# pixpi.net
KiCad netlist of a schematic drawn in EAGLE
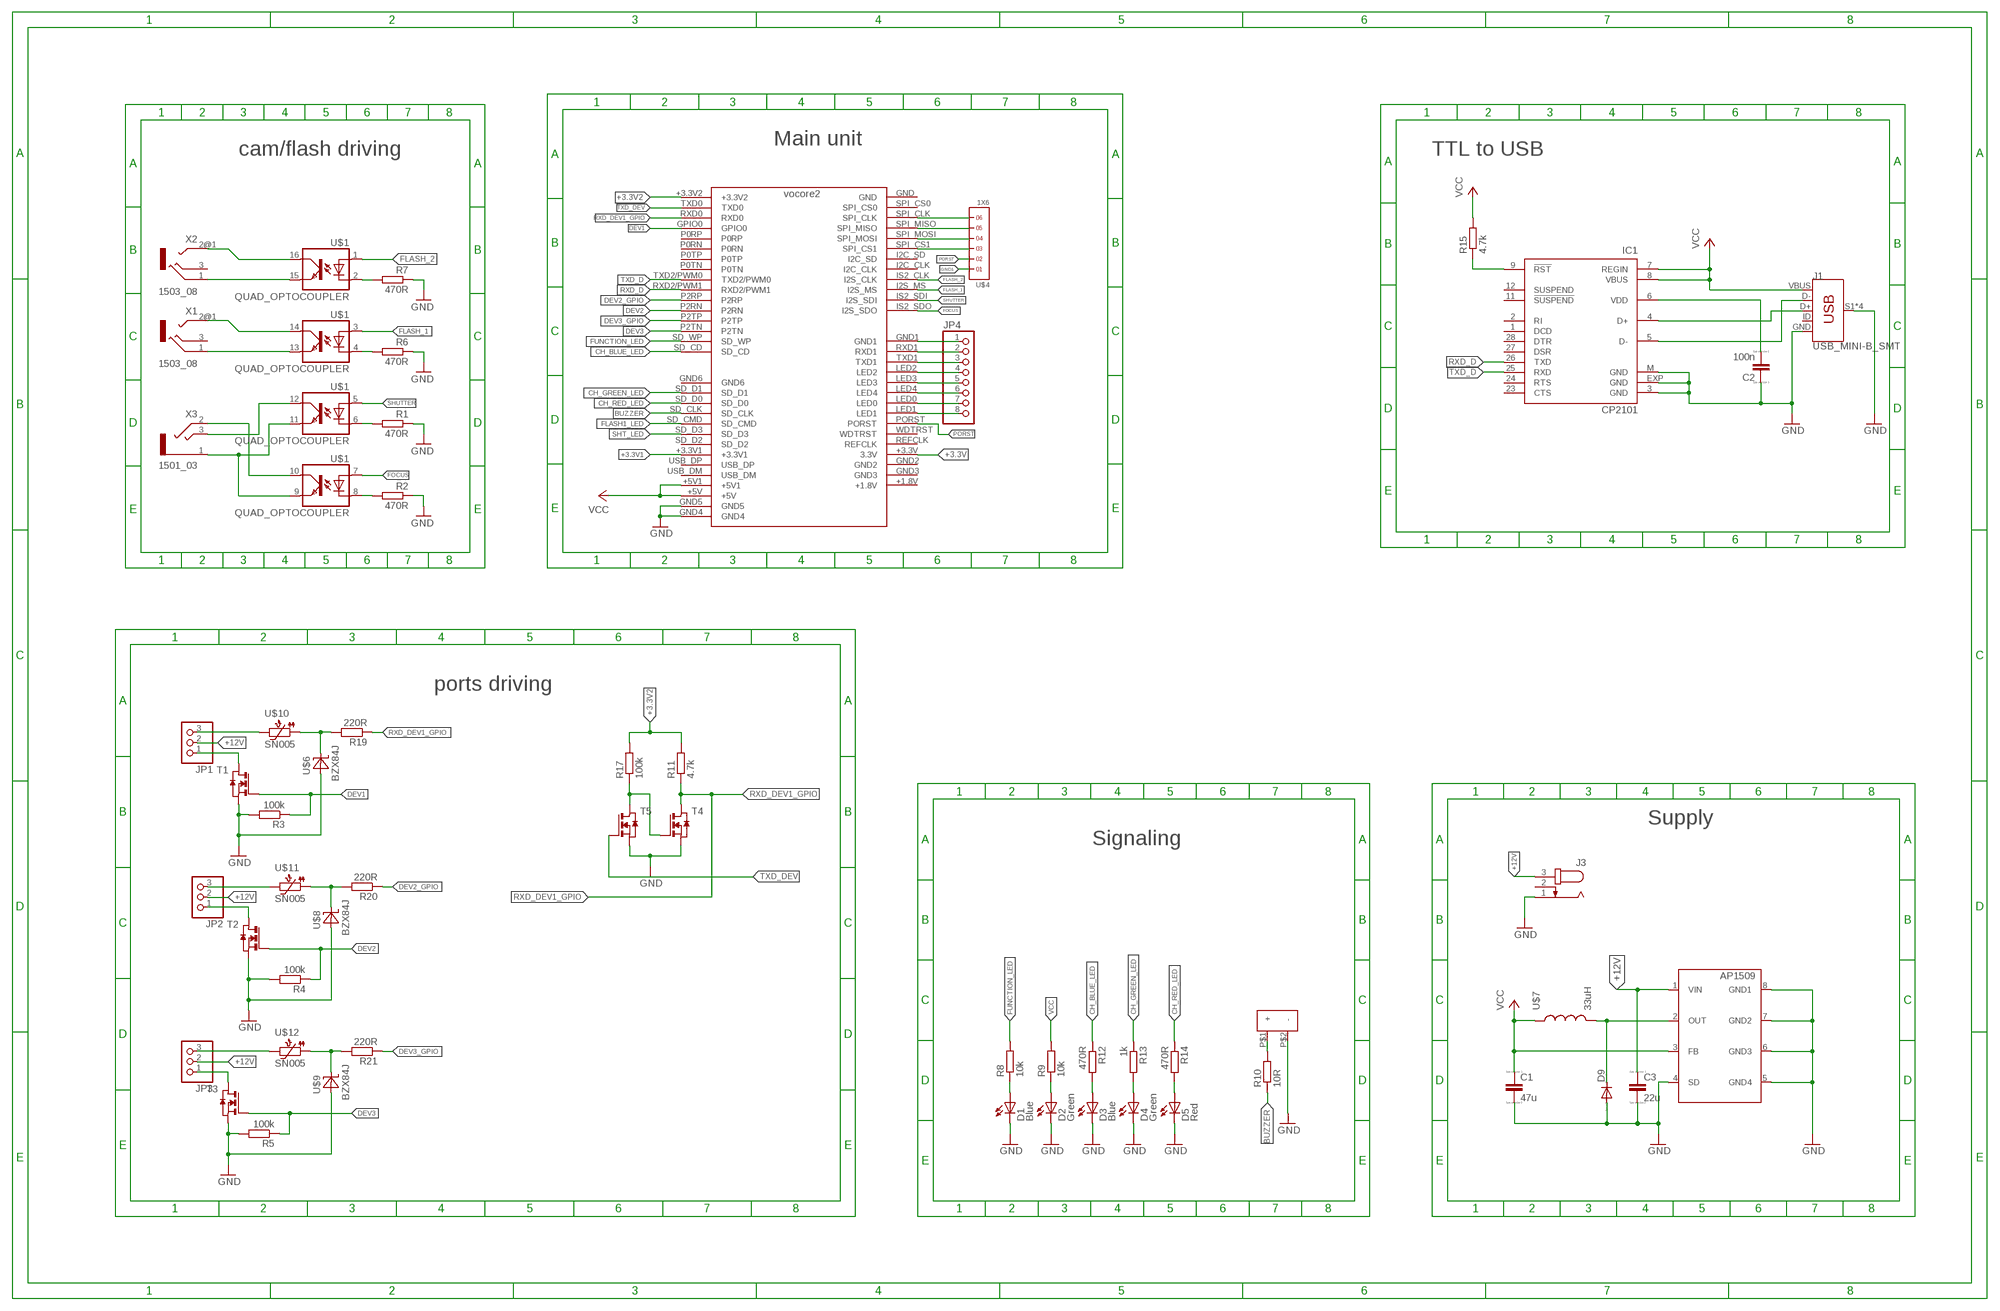
[diagram p0: schematic, sheet 1]

(export (version "E")
  (design (tool "Eeschema 10.0.6"))
  (components
    (comp (ref "C1")
      (value "47u")
      (footprint "eagle-import:C1210")
      (libsource (lib "eagle-import") (part "CC1210"))
    )
    (comp (ref "C2")
      (value "100n")
      (footprint "eagle-import:C0805")
      (libsource (lib "eagle-import") (part "C"))
    )
    (comp (ref "C3")
      (value "22u")
      (footprint "eagle-import:C1210")
      (libsource (lib "eagle-import") (part "CC1210"))
    )
    (comp (ref "D1")
      (value "Blue")
      (footprint "eagle-import:CHIPLED_0603")
      (fields (field (name "SPICEPREFIX") "D"))
      (libsource (lib "eagle-import") (part "LEDCHIPLED_0603"))
    )
    (comp (ref "D2")
      (value "Green")
      (footprint "eagle-import:CHIPLED_0603")
      (libsource (lib "eagle-import") (part "LEDCHIPLED_0603"))
    )
    (comp (ref "D3")
      (value "Blue")
      (footprint "eagle-import:CHIPLED_1206")
      (libsource (lib "eagle-import") (part "LEDCHIPLED_1206"))
    )
    (comp (ref "D4")
      (value "Green")
      (footprint "eagle-import:CHIPLED_1206")
      (libsource (lib "eagle-import") (part "LEDCHIPLED_1206"))
    )
    (comp (ref "D5")
      (value "Red")
      (footprint "eagle-import:CHIPLED_1206")
      (libsource (lib "eagle-import") (part "LEDCHIPLED_1206"))
    )
    (comp (ref "D9")
      (value "DIODE-SOD323-W")
      (footprint "eagle-import:SOD323-W")
      (libsource (lib "eagle-import") (part "DIODE-SOD323-W"))
    )
    (comp (ref "IC1")
      (value "CP2101")
      (footprint "eagle-import:MLP28")
      (fields (field (name "MF") "FARNELL") (field (name "MPN") "CP2102-GM"))
      (libsource (lib "eagle-import") (part "CP2101"))
    )
    (comp (ref "J1")
      (value "USB_MINI-B_SMT")
      (footprint "eagle-import:USB-MINIB")
      (libsource (lib "eagle-import") (part "USB_MINI-B_SMT"))
    )
    (comp (ref "J3")
      (value "JACK-PLUG0")
      (footprint "eagle-import:SPC4077")
      (libsource (lib "eagle-import") (part "JACK-PLUG0"))
    )
    (comp (ref "JP1")
      (value "PINHD-1X3/90")
      (footprint "eagle-import:1X03_90")
      (libsource (lib "eagle-import") (part "PINHD-1X3/90"))
    )
    (comp (ref "JP2")
      (value "PINHD-1X3/90")
      (footprint "eagle-import:1X03_90")
      (libsource (lib "eagle-import") (part "PINHD-1X3/90"))
    )
    (comp (ref "JP3")
      (value "PINHD-1X3/90")
      (footprint "eagle-import:1X03_90")
      (libsource (lib "eagle-import") (part "PINHD-1X3/90"))
    )
    (comp (ref "JP4")
      (value "PINHD-1X8")
      (footprint "eagle-import:1X08")
      (libsource (lib "eagle-import") (part "PINHD-1X8"))
    )
    (comp (ref "R1")
      (value "470R")
      (footprint "eagle-import:R0805")
      (libsource (lib "eagle-import") (part "R-EU_R0805"))
    )
    (comp (ref "R2")
      (value "470R")
      (footprint "eagle-import:R0805")
      (libsource (lib "eagle-import") (part "R-EU_R0805"))
    )
    (comp (ref "R3")
      (value "100k")
      (footprint "eagle-import:R0805")
      (libsource (lib "eagle-import") (part "R-EU_R0805"))
    )
    (comp (ref "R4")
      (value "100k")
      (footprint "eagle-import:R0805")
      (libsource (lib "eagle-import") (part "R-EU_R0805"))
    )
    (comp (ref "R5")
      (value "100k")
      (footprint "eagle-import:R0805")
      (libsource (lib "eagle-import") (part "R-EU_R0805"))
    )
    (comp (ref "R6")
      (value "470R")
      (footprint "eagle-import:R0805")
      (libsource (lib "eagle-import") (part "R-EU_R0805"))
    )
    (comp (ref "R7")
      (value "470R")
      (footprint "eagle-import:R0805")
      (libsource (lib "eagle-import") (part "R-EU_R0805"))
    )
    (comp (ref "R8")
      (value "10k")
      (footprint "eagle-import:R0805")
      (libsource (lib "eagle-import") (part "R-EU_R0805"))
    )
    (comp (ref "R9")
      (value "10k")
      (footprint "eagle-import:R0805")
      (libsource (lib "eagle-import") (part "R-EU_R0805"))
    )
    (comp (ref "R10")
      (value "10R")
      (footprint "eagle-import:R0805")
      (libsource (lib "eagle-import") (part "R-EU_R0805"))
    )
    (comp (ref "R11")
      (value "4.7k")
      (footprint "eagle-import:R0805")
      (libsource (lib "eagle-import") (part "R-EU_R0805"))
    )
    (comp (ref "R12")
      (value "470R")
      (footprint "eagle-import:R0805")
      (libsource (lib "eagle-import") (part "R-EU_R0805"))
    )
    (comp (ref "R13")
      (value "1k")
      (footprint "eagle-import:R0805")
      (libsource (lib "eagle-import") (part "R-EU_R0805"))
    )
    (comp (ref "R14")
      (value "470R")
      (footprint "eagle-import:R0805")
      (libsource (lib "eagle-import") (part "R-EU_R0805"))
    )
    (comp (ref "R15")
      (value "4.7k")
      (footprint "eagle-import:R0805")
      (libsource (lib "eagle-import") (part "R-EU_R0805"))
    )
    (comp (ref "R17")
      (value "100k")
      (footprint "eagle-import:R0805")
      (libsource (lib "eagle-import") (part "R-EU_R0805"))
    )
    (comp (ref "R19")
      (value "220R")
      (footprint "eagle-import:R0805")
      (libsource (lib "eagle-import") (part "R-EU_R0805"))
    )
    (comp (ref "R20")
      (value "220R")
      (footprint "eagle-import:R0805")
      (libsource (lib "eagle-import") (part "R-EU_R0805"))
    )
    (comp (ref "R21")
      (value "220R")
      (footprint "eagle-import:R0805")
      (libsource (lib "eagle-import") (part "R-EU_R0805"))
    )
    (comp (ref "T1")
      (value "NMOSSOT23")
      (footprint "eagle-import:SOT-23")
      (libsource (lib "eagle-import") (part "NMOSSOT23"))
    )
    (comp (ref "T2")
      (value "NMOSSOT23")
      (footprint "eagle-import:SOT-23")
      (libsource (lib "eagle-import") (part "NMOSSOT23"))
    )
    (comp (ref "T3")
      (value "NMOSSOT23")
      (footprint "eagle-import:SOT-23")
      (libsource (lib "eagle-import") (part "NMOSSOT23"))
    )
    (comp (ref "T4")
      (value "NMOSSOT23")
      (footprint "eagle-import:SOT-23")
      (libsource (lib "eagle-import") (part "NMOSSOT23"))
    )
    (comp (ref "T5")
      (value "NMOSSOT23")
      (footprint "eagle-import:SOT-23")
      (libsource (lib "eagle-import") (part "NMOSSOT23"))
    )
    (comp (ref "U$1")
      (value "QUAD_OPTOCOUPLER")
      (footprint "eagle-import:SO16")
      (libsource (lib "eagle-import") (part "QUAD_OPTOCOUPLER"))
    )
    (comp (ref "U$2")
      (value "VOCORE2")
      (footprint "eagle-import:VOCORE2")
      (libsource (lib "eagle-import") (part "VOCORE2"))
    )
    (comp (ref "U$3")
      (value "LD-BZEG-0905")
      (footprint "eagle-import:LD-BZEG-0905")
      (libsource (lib "eagle-import") (part "LD-BZEG-0905"))
    )
    (comp (ref "U$4")
      (value "1X6")
      (footprint "eagle-import:1X6")
      (libsource (lib "eagle-import") (part "1X6"))
    )
    (comp (ref "U$5")
      (value "AP1509")
      (footprint "eagle-import:SOP08")
      (libsource (lib "eagle-import") (part "AP1509"))
    )
    (comp (ref "U$6")
      (value "BZX84J")
      (footprint "eagle-import:SOD323_ST")
      (libsource (lib "eagle-import") (part "BZX84J"))
    )
    (comp (ref "U$7")
      (value "33uH")
      (footprint "eagle-import:DJNR6028")
      (libsource (lib "eagle-import") (part "DJNR6028"))
    )
    (comp (ref "U$8")
      (value "BZX84J")
      (footprint "eagle-import:SOD323_ST")
      (libsource (lib "eagle-import") (part "BZX84J"))
    )
    (comp (ref "U$9")
      (value "BZX84J")
      (footprint "eagle-import:SOD323_ST")
      (libsource (lib "eagle-import") (part "BZX84J"))
    )
    (comp (ref "U$10")
      (value "SN005")
      (footprint "eagle-import:R1206")
      (libsource (lib "eagle-import") (part "SN005"))
    )
    (comp (ref "U$11")
      (value "SN005")
      (footprint "eagle-import:R1206")
      (libsource (lib "eagle-import") (part "SN005"))
    )
    (comp (ref "U$12")
      (value "SN005")
      (footprint "eagle-import:R1206")
      (libsource (lib "eagle-import") (part "SN005"))
    )
    (comp (ref "X1")
      (value "1503_08")
      (footprint "eagle-import:1503_08")
      (libsource (lib "eagle-import") (part "1503_?08"))
    )
    (comp (ref "X2")
      (value "1503_08")
      (footprint "eagle-import:1503_08")
      (libsource (lib "eagle-import") (part "1503_?08"))
    )
    (comp (ref "X3")
      (value "1501_03")
      (footprint "eagle-import:1501_03")
      (libsource (lib "eagle-import") (part "1501_03"))
    )
  )
  (nets
    (net (code "1") (name "+3.3V") (class "Default")
      (node (ref "U$2") (pin "+3.3V") (pinfunction "3.3V_+3.3V") (pintype "bidirectional"))
    )
    (net (code "2") (name "+3.3V1") (class "Default")
      (node (ref "U$2") (pin "+3.3V1") (pinfunction "+3.3V1_+3.3V1") (pintype "bidirectional"))
    )
    (net (code "3") (name "+3.3V2") (class "Default")
      (node (ref "R11") (pin "2") (pinfunction "2_2") (pintype "passive"))
      (node (ref "R17") (pin "2") (pinfunction "2_2") (pintype "passive"))
      (node (ref "U$2") (pin "+3.3V2") (pinfunction "+3.3V2_+3.3V2") (pintype "bidirectional"))
    )
    (net (code "4") (name "+12V") (class "Default")
      (node (ref "C3") (pin "1") (pinfunction "1_1") (pintype "passive"))
      (node (ref "J3") (pin "3") (pinfunction "3_3") (pintype "passive"))
      (node (ref "JP1") (pin "2") (pinfunction "2_2") (pintype "passive"))
      (node (ref "JP2") (pin "2") (pinfunction "2_2") (pintype "passive"))
      (node (ref "JP3") (pin "2") (pinfunction "2_2") (pintype "passive"))
      (node (ref "U$5") (pin "1") (pinfunction "VIN_1") (pintype "bidirectional"))
    )
    (net (code "5") (name "BUZZER") (class "Default")
      (node (ref "R10") (pin "1") (pinfunction "1_1") (pintype "passive"))
      (node (ref "U$2") (pin "SD_CLK") (pinfunction "SD_CLK_SD_CLK") (pintype "bidirectional"))
    )
    (net (code "6") (name "CH_BLUE_LED") (class "Default")
      (node (ref "R12") (pin "1") (pinfunction "1_1") (pintype "passive"))
      (node (ref "U$2") (pin "SD_CD") (pinfunction "SD_CD_SD_CD") (pintype "bidirectional"))
    )
    (net (code "7") (name "CH_GREEN_LED") (class "Default")
      (node (ref "R13") (pin "1") (pinfunction "1_1") (pintype "passive"))
      (node (ref "U$2") (pin "SD_D1") (pinfunction "SD_D1_SD_D1") (pintype "bidirectional"))
    )
    (net (code "8") (name "CH_RED_LED") (class "Default")
      (node (ref "R14") (pin "1") (pinfunction "1_1") (pintype "passive"))
      (node (ref "U$2") (pin "SD_D0") (pinfunction "SD_D0_SD_D0") (pintype "bidirectional"))
    )
    (net (code "9") (name "DEV1") (class "Default")
      (node (ref "R3") (pin "1") (pinfunction "1_1") (pintype "passive"))
      (node (ref "T1") (pin "3") (pinfunction "G_3") (pintype "passive"))
      (node (ref "U$2") (pin "GPIO0") (pinfunction "GPIO0_GPIO0") (pintype "bidirectional"))
    )
    (net (code "10") (name "DEV2") (class "Default")
      (node (ref "R4") (pin "1") (pinfunction "1_1") (pintype "passive"))
      (node (ref "T2") (pin "3") (pinfunction "G_3") (pintype "passive"))
      (node (ref "U$2") (pin "P2RN") (pinfunction "P2RN_P2RN") (pintype "bidirectional"))
    )
    (net (code "11") (name "DEV2_GPIO") (class "Default")
      (node (ref "R20") (pin "1") (pinfunction "1_1") (pintype "passive"))
      (node (ref "U$2") (pin "P2RP") (pinfunction "P2RP_P2RP") (pintype "bidirectional"))
    )
    (net (code "12") (name "DEV3") (class "Default")
      (node (ref "R5") (pin "1") (pinfunction "1_1") (pintype "passive"))
      (node (ref "T3") (pin "3") (pinfunction "G_3") (pintype "passive"))
      (node (ref "U$2") (pin "P2TN") (pinfunction "P2TN_P2TN") (pintype "bidirectional"))
    )
    (net (code "13") (name "DEV3_GPIO") (class "Default")
      (node (ref "R21") (pin "1") (pinfunction "1_1") (pintype "passive"))
      (node (ref "U$2") (pin "P2TP") (pinfunction "P2TP_P2TP") (pintype "bidirectional"))
    )
    (net (code "14") (name "FLASH1_LED") (class "Default")
      (node (ref "U$2") (pin "SD_CMD") (pinfunction "SD_CMD_SD_CMD") (pintype "bidirectional"))
    )
    (net (code "15") (name "FLASH_1") (class "Default")
      (node (ref "U$1") (pin "3") (pinfunction "A1_3") (pintype "passive"))
      (node (ref "U$2") (pin "I2S_MS") (pinfunction "I2S_MS_I2S_MS") (pintype "bidirectional"))
    )
    (net (code "16") (name "FLASH_2") (class "Default")
      (node (ref "U$1") (pin "1") (pinfunction "A_1") (pintype "passive"))
      (node (ref "U$2") (pin "IS2_CLK") (pinfunction "I2S_CLK_IS2_CLK") (pintype "bidirectional"))
    )
    (net (code "17") (name "FOCUS") (class "Default")
      (node (ref "U$1") (pin "7") (pinfunction "A3_7") (pintype "passive"))
      (node (ref "U$2") (pin "IS2_SDO") (pinfunction "I2S_SDO_IS2_SDO") (pintype "bidirectional"))
    )
    (net (code "18") (name "FUNCTION_LED") (class "Default")
      (node (ref "R8") (pin "2") (pinfunction "2_2") (pintype "passive"))
      (node (ref "U$2") (pin "SD_WP") (pinfunction "SD_WP_SD_WP") (pintype "bidirectional"))
    )
    (net (code "19") (name "GND") (class "Default")
      (node (ref "C1") (pin "2") (pinfunction "2_2") (pintype "passive"))
      (node (ref "C2") (pin "1") (pinfunction "1_1") (pintype "passive"))
      (node (ref "C3") (pin "2") (pinfunction "2_2") (pintype "passive"))
      (node (ref "D1") (pin "C") (pinfunction "C_C") (pintype "passive"))
      (node (ref "D2") (pin "C") (pinfunction "C_C") (pintype "passive"))
      (node (ref "D3") (pin "C") (pinfunction "C_C") (pintype "passive"))
      (node (ref "D4") (pin "C") (pinfunction "C_C") (pintype "passive"))
      (node (ref "D5") (pin "C") (pinfunction "C_C") (pintype "passive"))
      (node (ref "D9") (pin "A") (pinfunction "A_A") (pintype "passive"))
      (node (ref "IC1") (pin "3") (pinfunction "GND_3") (pintype "power_in"))
      (node (ref "IC1") (pin "EXP") (pinfunction "GND_EXP") (pintype "power_in"))
      (node (ref "IC1") (pin "M") (pinfunction "GND_M") (pintype "power_in"))
      (node (ref "J1") (pin "GND") (pinfunction "GND_GND") (pintype "power_in"))
      (node (ref "J1") (pin "S1") (pinfunction "SHIELD_S1") (pintype "bidirectional"))
      (node (ref "J1") (pin "S2") (pinfunction "SHIELD_S2") (pintype "bidirectional"))
      (node (ref "J1") (pin "S3") (pinfunction "SHIELD_S3") (pintype "bidirectional"))
      (node (ref "J1") (pin "S4") (pinfunction "SHIELD_S4") (pintype "bidirectional"))
      (node (ref "J3") (pin "1") (pinfunction "1_1") (pintype "passive"))
      (node (ref "R1") (pin "1") (pinfunction "1_1") (pintype "passive"))
      (node (ref "R2") (pin "1") (pinfunction "1_1") (pintype "passive"))
      (node (ref "R3") (pin "2") (pinfunction "2_2") (pintype "passive"))
      (node (ref "R4") (pin "2") (pinfunction "2_2") (pintype "passive"))
      (node (ref "R5") (pin "2") (pinfunction "2_2") (pintype "passive"))
      (node (ref "R6") (pin "1") (pinfunction "1_1") (pintype "passive"))
      (node (ref "R7") (pin "1") (pinfunction "1_1") (pintype "passive"))
      (node (ref "T1") (pin "2") (pinfunction "S_2") (pintype "passive"))
      (node (ref "T2") (pin "2") (pinfunction "S_2") (pintype "passive"))
      (node (ref "T3") (pin "2") (pinfunction "S_2") (pintype "passive"))
      (node (ref "T4") (pin "2") (pinfunction "S_2") (pintype "passive"))
      (node (ref "T5") (pin "2") (pinfunction "S_2") (pintype "passive"))
      (node (ref "U$2") (pin "GND4") (pinfunction "GND4_GND4") (pintype "bidirectional"))
      (node (ref "U$2") (pin "GND5") (pinfunction "GND5_GND5") (pintype "bidirectional"))
      (node (ref "U$3") (pin "P$2") (pinfunction "-_P$2") (pintype "bidirectional"))
      (node (ref "U$5") (pin "4") (pinfunction "SD_4") (pintype "bidirectional"))
      (node (ref "U$5") (pin "5") (pinfunction "GND4_5") (pintype "bidirectional"))
      (node (ref "U$5") (pin "6") (pinfunction "GND3_6") (pintype "bidirectional"))
      (node (ref "U$5") (pin "7") (pinfunction "GND2_7") (pintype "bidirectional"))
      (node (ref "U$5") (pin "8") (pinfunction "GND1_8") (pintype "bidirectional"))
      (node (ref "U$6") (pin "A") (pinfunction "A_A") (pintype "passive"))
      (node (ref "U$8") (pin "A") (pinfunction "A_A") (pintype "passive"))
      (node (ref "U$9") (pin "A") (pinfunction "A_A") (pintype "passive"))
    )
    (net (code "20") (name "GND1") (class "Default")
      (node (ref "JP4") (pin "1") (pinfunction "1_1") (pintype "passive"))
      (node (ref "U$2") (pin "GND1") (pinfunction "GND1_GND1") (pintype "bidirectional"))
      (node (ref "U$4") (pin "1") (pinfunction "1_1") (pintype "bidirectional"))
    )
    (net (code "21") (name "Net-(D1-PadA)") (class "Default")
      (node (ref "D1") (pin "A") (pinfunction "A_A") (pintype "passive"))
      (node (ref "R8") (pin "1") (pinfunction "1_1") (pintype "passive"))
    )
    (net (code "22") (name "Net-(D2-PadA)") (class "Default")
      (node (ref "D2") (pin "A") (pinfunction "A_A") (pintype "passive"))
      (node (ref "R9") (pin "1") (pinfunction "1_1") (pintype "passive"))
    )
    (net (code "23") (name "Net-(D3-PadA)") (class "Default")
      (node (ref "D3") (pin "A") (pinfunction "A_A") (pintype "passive"))
      (node (ref "R12") (pin "2") (pinfunction "2_2") (pintype "passive"))
    )
    (net (code "24") (name "Net-(D4-PadA)") (class "Default")
      (node (ref "D4") (pin "A") (pinfunction "A_A") (pintype "passive"))
      (node (ref "R13") (pin "2") (pinfunction "2_2") (pintype "passive"))
    )
    (net (code "25") (name "Net-(D5-PadA)") (class "Default")
      (node (ref "D5") (pin "A") (pinfunction "A_A") (pintype "passive"))
      (node (ref "R14") (pin "2") (pinfunction "2_2") (pintype "passive"))
    )
    (net (code "26") (name "Net-(IC1-D+)") (class "Default")
      (node (ref "IC1") (pin "4") (pinfunction "D+_4") (pintype "bidirectional"))
      (node (ref "J1") (pin "D+") (pinfunction "D+_D+") (pintype "bidirectional"))
    )
    (net (code "27") (name "Net-(IC1-D-)") (class "Default")
      (node (ref "IC1") (pin "5") (pinfunction "D-_5") (pintype "bidirectional"))
      (node (ref "J1") (pin "D-") (pinfunction "D-_D-") (pintype "bidirectional"))
    )
    (net (code "28") (name "Net-(IC1-VDD)") (class "Default")
      (node (ref "C2") (pin "2") (pinfunction "2_2") (pintype "passive"))
      (node (ref "IC1") (pin "6") (pinfunction "VDD_6") (pintype "power_in"))
    )
    (net (code "29") (name "Net-(IC1-~{RST})") (class "Default")
      (node (ref "IC1") (pin "9") (pinfunction "~{RST}_9") (pintype "bidirectional"))
      (node (ref "R15") (pin "1") (pinfunction "1_1") (pintype "passive"))
    )
    (net (code "30") (name "Net-(JP1-Pad3)") (class "Default")
      (node (ref "JP1") (pin "3") (pinfunction "3_3") (pintype "passive"))
      (node (ref "U$10") (pin "2") (pinfunction "2_2") (pintype "passive"))
    )
    (net (code "31") (name "Net-(JP2-Pad3)") (class "Default")
      (node (ref "JP2") (pin "3") (pinfunction "3_3") (pintype "passive"))
      (node (ref "U$11") (pin "2") (pinfunction "2_2") (pintype "passive"))
    )
    (net (code "32") (name "Net-(JP3-Pad3)") (class "Default")
      (node (ref "JP3") (pin "3") (pinfunction "3_3") (pintype "passive"))
      (node (ref "U$12") (pin "2") (pinfunction "2_2") (pintype "passive"))
    )
    (net (code "33") (name "Net-(JP4-Pad2)") (class "Default")
      (node (ref "JP4") (pin "2") (pinfunction "2_2") (pintype "passive"))
      (node (ref "U$2") (pin "RXD1") (pinfunction "RXD1_RXD1") (pintype "bidirectional"))
    )
    (net (code "34") (name "Net-(JP4-Pad3)") (class "Default")
      (node (ref "JP4") (pin "3") (pinfunction "3_3") (pintype "passive"))
      (node (ref "U$2") (pin "TXD1") (pinfunction "TXD1_TXD1") (pintype "bidirectional"))
    )
    (net (code "35") (name "Net-(JP4-Pad4)") (class "Default")
      (node (ref "JP4") (pin "4") (pinfunction "4_4") (pintype "passive"))
      (node (ref "U$2") (pin "LED2") (pinfunction "LED2_LED2") (pintype "bidirectional"))
    )
    (net (code "36") (name "Net-(JP4-Pad5)") (class "Default")
      (node (ref "JP4") (pin "5") (pinfunction "5_5") (pintype "passive"))
      (node (ref "U$2") (pin "LED3") (pinfunction "LED3_LED3") (pintype "bidirectional"))
    )
    (net (code "37") (name "Net-(JP4-Pad6)") (class "Default")
      (node (ref "JP4") (pin "6") (pinfunction "6_6") (pintype "passive"))
      (node (ref "U$2") (pin "LED4") (pinfunction "LED4_LED4") (pintype "bidirectional"))
    )
    (net (code "38") (name "Net-(JP4-Pad7)") (class "Default")
      (node (ref "JP4") (pin "7") (pinfunction "7_7") (pintype "passive"))
      (node (ref "U$2") (pin "LED0") (pinfunction "LED0_LED0") (pintype "bidirectional"))
    )
    (net (code "39") (name "Net-(JP4-Pad8)") (class "Default")
      (node (ref "JP4") (pin "8") (pinfunction "8_8") (pintype "passive"))
      (node (ref "U$2") (pin "LED1") (pinfunction "LED1_LED1") (pintype "bidirectional"))
    )
    (net (code "40") (name "Net-(R19-Pad2)") (class "Default")
      (node (ref "R19") (pin "2") (pinfunction "2_2") (pintype "passive"))
      (node (ref "U$10") (pin "1") (pinfunction "1_1") (pintype "passive"))
      (node (ref "U$6") (pin "C") (pinfunction "C_C") (pintype "passive"))
    )
    (net (code "41") (name "Net-(R20-Pad2)") (class "Default")
      (node (ref "R20") (pin "2") (pinfunction "2_2") (pintype "passive"))
      (node (ref "U$11") (pin "1") (pinfunction "1_1") (pintype "passive"))
      (node (ref "U$8") (pin "C") (pinfunction "C_C") (pintype "passive"))
    )
    (net (code "42") (name "Net-(R21-Pad2)") (class "Default")
      (node (ref "R21") (pin "2") (pinfunction "2_2") (pintype "passive"))
      (node (ref "U$12") (pin "1") (pinfunction "1_1") (pintype "passive"))
      (node (ref "U$9") (pin "C") (pinfunction "C_C") (pintype "passive"))
    )
    (net (code "43") (name "Net-(T1-D)") (class "Default")
      (node (ref "JP1") (pin "1") (pinfunction "1_1") (pintype "passive"))
      (node (ref "T1") (pin "1") (pinfunction "D_1") (pintype "passive"))
    )
    (net (code "44") (name "Net-(T2-D)") (class "Default")
      (node (ref "JP2") (pin "1") (pinfunction "1_1") (pintype "passive"))
      (node (ref "T2") (pin "1") (pinfunction "D_1") (pintype "passive"))
    )
    (net (code "45") (name "Net-(T3-D)") (class "Default")
      (node (ref "JP3") (pin "1") (pinfunction "1_1") (pintype "passive"))
      (node (ref "T3") (pin "1") (pinfunction "D_1") (pintype "passive"))
    )
    (net (code "46") (name "Net-(T4-G)") (class "Default")
      (node (ref "R17") (pin "1") (pinfunction "1_1") (pintype "passive"))
      (node (ref "T4") (pin "3") (pinfunction "G_3") (pintype "passive"))
      (node (ref "T5") (pin "1") (pinfunction "D_1") (pintype "passive"))
    )
    (net (code "47") (name "Net-(U$1-C)") (class "Default")
      (node (ref "R7") (pin "2") (pinfunction "2_2") (pintype "passive"))
      (node (ref "U$1") (pin "2") (pinfunction "C_2") (pintype "passive"))
    )
    (net (code "48") (name "Net-(U$1-C1)") (class "Default")
      (node (ref "R6") (pin "2") (pinfunction "2_2") (pintype "passive"))
      (node (ref "U$1") (pin "4") (pinfunction "C1_4") (pintype "passive"))
    )
    (net (code "49") (name "Net-(U$1-C2)") (class "Default")
      (node (ref "R1") (pin "2") (pinfunction "2_2") (pintype "passive"))
      (node (ref "U$1") (pin "6") (pinfunction "C2_6") (pintype "passive"))
    )
    (net (code "50") (name "Net-(U$1-C3)") (class "Default")
      (node (ref "R2") (pin "2") (pinfunction "2_2") (pintype "passive"))
      (node (ref "U$1") (pin "8") (pinfunction "C3_8") (pintype "passive"))
    )
    (net (code "51") (name "Net-(U$1-COL)") (class "Default")
      (node (ref "U$1") (pin "16") (pinfunction "COL_16") (pintype "passive"))
      (node (ref "X2") (pin "2@1") (pinfunction "2_2@1") (pintype "passive"))
    )
    (net (code "52") (name "Net-(U$1-COL1)") (class "Default")
      (node (ref "U$1") (pin "14") (pinfunction "COL1_14") (pintype "passive"))
      (node (ref "X1") (pin "2@1") (pinfunction "2_2@1") (pintype "passive"))
    )
    (net (code "53") (name "Net-(U$1-COL2)") (class "Default")
      (node (ref "U$1") (pin "12") (pinfunction "COL2_12") (pintype "passive"))
      (node (ref "X3") (pin "3") (pinfunction "3_3") (pintype "passive"))
    )
    (net (code "54") (name "Net-(U$1-COL3)") (class "Default")
      (node (ref "U$1") (pin "10") (pinfunction "COL3_10") (pintype "passive"))
      (node (ref "X3") (pin "2") (pinfunction "2_2") (pintype "passive"))
    )
    (net (code "55") (name "Net-(U$1-EMIT)") (class "Default")
      (node (ref "U$1") (pin "15") (pinfunction "EMIT_15") (pintype "passive"))
      (node (ref "X2") (pin "1") (pinfunction "1_1") (pintype "passive"))
    )
    (net (code "56") (name "Net-(U$1-EMIT1)") (class "Default")
      (node (ref "U$1") (pin "13") (pinfunction "EMIT1_13") (pintype "passive"))
      (node (ref "X1") (pin "1") (pinfunction "1_1") (pintype "passive"))
    )
    (net (code "57") (name "Net-(U$1-EMIT2)") (class "Default")
      (node (ref "U$1") (pin "11") (pinfunction "EMIT2_11") (pintype "passive"))
      (node (ref "U$1") (pin "9") (pinfunction "EMIT3_9") (pintype "passive"))
      (node (ref "X3") (pin "1") (pinfunction "1_1") (pintype "passive"))
    )
    (net (code "58") (name "Net-(U$2-PadSPI_CLK)") (class "Default")
      (node (ref "U$2") (pin "SPI_CLK") (pinfunction "SPI_CLK_SPI_CLK") (pintype "bidirectional"))
      (node (ref "U$4") (pin "6") (pinfunction "6_6") (pintype "bidirectional"))
    )
    (net (code "59") (name "Net-(U$2-PadSPI_CS1)") (class "Default")
      (node (ref "U$2") (pin "SPI_CS1") (pinfunction "SPI_CS1_SPI_CS1") (pintype "bidirectional"))
      (node (ref "U$4") (pin "3") (pinfunction "3_3") (pintype "bidirectional"))
    )
    (net (code "60") (name "Net-(U$2-PadSPI_MISO)") (class "Default")
      (node (ref "U$2") (pin "SPI_MISO") (pinfunction "SPI_MISO_SPI_MISO") (pintype "bidirectional"))
      (node (ref "U$4") (pin "5") (pinfunction "5_5") (pintype "bidirectional"))
    )
    (net (code "61") (name "Net-(U$2-PadSPI_MOSI)") (class "Default")
      (node (ref "U$2") (pin "SPI_MOSI") (pinfunction "SPI_MOSI_SPI_MOSI") (pintype "bidirectional"))
      (node (ref "U$4") (pin "4") (pinfunction "4_4") (pintype "bidirectional"))
    )
    (net (code "62") (name "Net-(U$3-+)") (class "Default")
      (node (ref "R10") (pin "2") (pinfunction "2_2") (pintype "passive"))
      (node (ref "U$3") (pin "P$1") (pinfunction "+_P$1") (pintype "bidirectional"))
    )
    (net (code "63") (name "Net-(U$5-OUT)") (class "Default")
      (node (ref "D9") (pin "C") (pinfunction "C_C") (pintype "passive"))
      (node (ref "U$5") (pin "2") (pinfunction "OUT_2") (pintype "bidirectional"))
      (node (ref "U$7") (pin "P$4") (pinfunction "2_P$4") (pintype "passive"))
    )
    (net (code "64") (name "PORST") (class "Default")
      (node (ref "U$2") (pin "PORST") (pinfunction "PORST_PORST") (pintype "bidirectional"))
      (node (ref "U$4") (pin "2") (pinfunction "2_2") (pintype "bidirectional"))
    )
    (net (code "65") (name "RXD_D") (class "Default")
      (node (ref "IC1") (pin "26") (pinfunction "TXD_26") (pintype "output"))
      (node (ref "U$2") (pin "RXD2/PWM1") (pinfunction "RXD2/PWM1_RXD2/PWM1") (pintype "bidirectional"))
    )
    (net (code "66") (name "RXD_DEV1_GPIO") (class "Default")
      (node (ref "R11") (pin "1") (pinfunction "1_1") (pintype "passive"))
      (node (ref "R19") (pin "1") (pinfunction "1_1") (pintype "passive"))
      (node (ref "T4") (pin "1") (pinfunction "D_1") (pintype "passive"))
      (node (ref "U$2") (pin "RXD0") (pinfunction "RXD0_RXD0") (pintype "bidirectional"))
    )
    (net (code "67") (name "SHT_LED") (class "Default")
      (node (ref "U$2") (pin "SD_D3") (pinfunction "SD_D3_SD_D3") (pintype "bidirectional"))
    )
    (net (code "68") (name "SHUTTER") (class "Default")
      (node (ref "U$1") (pin "5") (pinfunction "A2_5") (pintype "passive"))
      (node (ref "U$2") (pin "IS2_SDI") (pinfunction "I2S_SDI_IS2_SDI") (pintype "bidirectional"))
    )
    (net (code "69") (name "TXD_D") (class "Default")
      (node (ref "IC1") (pin "25") (pinfunction "RXD_25") (pintype "input"))
      (node (ref "U$2") (pin "TXD2/PWM0") (pinfunction "TXD2/PWM0_TXD2/PWM0") (pintype "bidirectional"))
    )
    (net (code "70") (name "TXD_DEV") (class "Default")
      (node (ref "T5") (pin "3") (pinfunction "G_3") (pintype "passive"))
      (node (ref "U$2") (pin "TXD0") (pinfunction "TXD0_TXD0") (pintype "bidirectional"))
    )
    (net (code "71") (name "VCC") (class "Default")
      (node (ref "C1") (pin "1") (pinfunction "1_1") (pintype "passive"))
      (node (ref "IC1") (pin "7") (pinfunction "REGIN_7") (pintype "passive"))
      (node (ref "IC1") (pin "8") (pinfunction "VBUS_8") (pintype "input"))
      (node (ref "J1") (pin "VBUS") (pinfunction "VBUS_VBUS") (pintype "power_in"))
      (node (ref "R15") (pin "2") (pinfunction "2_2") (pintype "passive"))
      (node (ref "R9") (pin "2") (pinfunction "2_2") (pintype "passive"))
      (node (ref "U$2") (pin "+5V") (pinfunction "+5V_+5V") (pintype "bidirectional"))
      (node (ref "U$2") (pin "+5V1") (pinfunction "+5V1_+5V1") (pintype "bidirectional"))
      (node (ref "U$5") (pin "3") (pinfunction "FB_3") (pintype "bidirectional"))
      (node (ref "U$7") (pin "P$3") (pinfunction "1_P$3") (pintype "passive"))
    )
    (net (code "72") (name "unconnected-(IC1-CTS-Pad23)") (class "Default")
      (node (ref "IC1") (pin "23") (pinfunction "CTS_23") (pintype "input"))
    )
    (net (code "73") (name "unconnected-(IC1-DCD-Pad1)") (class "Default")
      (node (ref "IC1") (pin "1") (pinfunction "DCD_1") (pintype "input"))
    )
    (net (code "74") (name "unconnected-(IC1-DSR-Pad27)") (class "Default")
      (node (ref "IC1") (pin "27") (pinfunction "DSR_27") (pintype "input"))
    )
    (net (code "75") (name "unconnected-(IC1-DTR-Pad28)") (class "Default")
      (node (ref "IC1") (pin "28") (pinfunction "DTR_28") (pintype "output"))
    )
    (net (code "76") (name "unconnected-(IC1-RI-Pad2)") (class "Default")
      (node (ref "IC1") (pin "2") (pinfunction "RI_2") (pintype "input"))
    )
    (net (code "77") (name "unconnected-(IC1-RTS-Pad24)") (class "Default")
      (node (ref "IC1") (pin "24") (pinfunction "RTS_24") (pintype "output"))
    )
    (net (code "78") (name "unconnected-(IC1-SUSPEND-Pad12)") (class "Default")
      (node (ref "IC1") (pin "12") (pinfunction "SUSPEND_12") (pintype "output"))
    )
    (net (code "79") (name "unconnected-(IC1-~{SUSPEND}-Pad11)") (class "Default")
      (node (ref "IC1") (pin "11") (pinfunction "~{SUSPEND}_11") (pintype "output"))
    )
    (net (code "80") (name "unconnected-(J1-PadID)") (class "Default")
      (node (ref "J1") (pin "ID") (pinfunction "ID_ID") (pintype "bidirectional"))
    )
    (net (code "81") (name "unconnected-(J3-Pad2)") (class "Default")
      (node (ref "J3") (pin "2") (pinfunction "2_2") (pintype "passive"))
    )
    (net (code "82") (name "unconnected-(U$2-Pad+1.8V)") (class "Default")
      (node (ref "U$2") (pin "+1.8V") (pinfunction "+1.8V_+1.8V") (pintype "bidirectional"))
    )
    (net (code "83") (name "unconnected-(U$2-PadGND)") (class "Default")
      (node (ref "U$2") (pin "GND") (pinfunction "GND_GND") (pintype "bidirectional"))
    )
    (net (code "84") (name "unconnected-(U$2-PadGND2)") (class "Default")
      (node (ref "U$2") (pin "GND2") (pinfunction "GND2_GND2") (pintype "bidirectional"))
    )
    (net (code "85") (name "unconnected-(U$2-PadGND3)") (class "Default")
      (node (ref "U$2") (pin "GND3") (pinfunction "GND3_GND3") (pintype "bidirectional"))
    )
    (net (code "86") (name "unconnected-(U$2-PadGND6)") (class "Default")
      (node (ref "U$2") (pin "GND6") (pinfunction "GND6_GND6") (pintype "bidirectional"))
    )
    (net (code "87") (name "unconnected-(U$2-PadI2C_CLK)") (class "Default")
      (node (ref "U$2") (pin "I2C_CLK") (pinfunction "I2C_CLK_I2C_CLK") (pintype "bidirectional"))
    )
    (net (code "88") (name "unconnected-(U$2-PadI2C_SD)") (class "Default")
      (node (ref "U$2") (pin "I2C_SD") (pinfunction "I2C_SD_I2C_SD") (pintype "bidirectional"))
    )
    (net (code "89") (name "unconnected-(U$2-PadP0RN)") (class "Default")
      (node (ref "U$2") (pin "P0RN") (pinfunction "P0RN_P0RN") (pintype "bidirectional"))
    )
    (net (code "90") (name "unconnected-(U$2-PadP0RP)") (class "Default")
      (node (ref "U$2") (pin "P0RP") (pinfunction "P0RP_P0RP") (pintype "bidirectional"))
    )
    (net (code "91") (name "unconnected-(U$2-PadP0TN)") (class "Default")
      (node (ref "U$2") (pin "P0TN") (pinfunction "P0TN_P0TN") (pintype "bidirectional"))
    )
    (net (code "92") (name "unconnected-(U$2-PadP0TP)") (class "Default")
      (node (ref "U$2") (pin "P0TP") (pinfunction "P0TP_P0TP") (pintype "bidirectional"))
    )
    (net (code "93") (name "unconnected-(U$2-PadREFCLK)") (class "Default")
      (node (ref "U$2") (pin "REFCLK") (pinfunction "REFCLK_REFCLK") (pintype "bidirectional"))
    )
    (net (code "94") (name "unconnected-(U$2-PadSD_D2)") (class "Default")
      (node (ref "U$2") (pin "SD_D2") (pinfunction "SD_D2_SD_D2") (pintype "bidirectional"))
    )
    (net (code "95") (name "unconnected-(U$2-PadSPI_CS0)") (class "Default")
      (node (ref "U$2") (pin "SPI_CS0") (pinfunction "SPI_CS0_SPI_CS0") (pintype "bidirectional"))
    )
    (net (code "96") (name "unconnected-(U$2-PadUSB_DM)") (class "Default")
      (node (ref "U$2") (pin "USB_DM") (pinfunction "USB_DM_USB_DM") (pintype "bidirectional"))
    )
    (net (code "97") (name "unconnected-(U$2-PadUSB_DP)") (class "Default")
      (node (ref "U$2") (pin "USB_DP") (pinfunction "USB_DP_USB_DP") (pintype "bidirectional"))
    )
    (net (code "98") (name "unconnected-(U$2-PadWDTRST)") (class "Default")
      (node (ref "U$2") (pin "WDTRST") (pinfunction "WDTRST_WDTRST") (pintype "bidirectional"))
    )
    (net (code "99") (name "unconnected-(X1-2-Pad2@2)") (class "Default")
      (node (ref "X1") (pin "2@2") (pinfunction "2_2@2") (pintype "passive"))
    )
    (net (code "100") (name "unconnected-(X1-Pad3)") (class "Default")
      (node (ref "X1") (pin "3") (pinfunction "3_3") (pintype "passive"))
    )
    (net (code "101") (name "unconnected-(X2-2-Pad2@2)") (class "Default")
      (node (ref "X2") (pin "2@2") (pinfunction "2_2@2") (pintype "passive"))
    )
    (net (code "102") (name "unconnected-(X2-Pad3)") (class "Default")
      (node (ref "X2") (pin "3") (pinfunction "3_3") (pintype "passive"))
    )
  )
)
